# ESC.net
KiCad netlist of a schematic drawn in Altium Designer
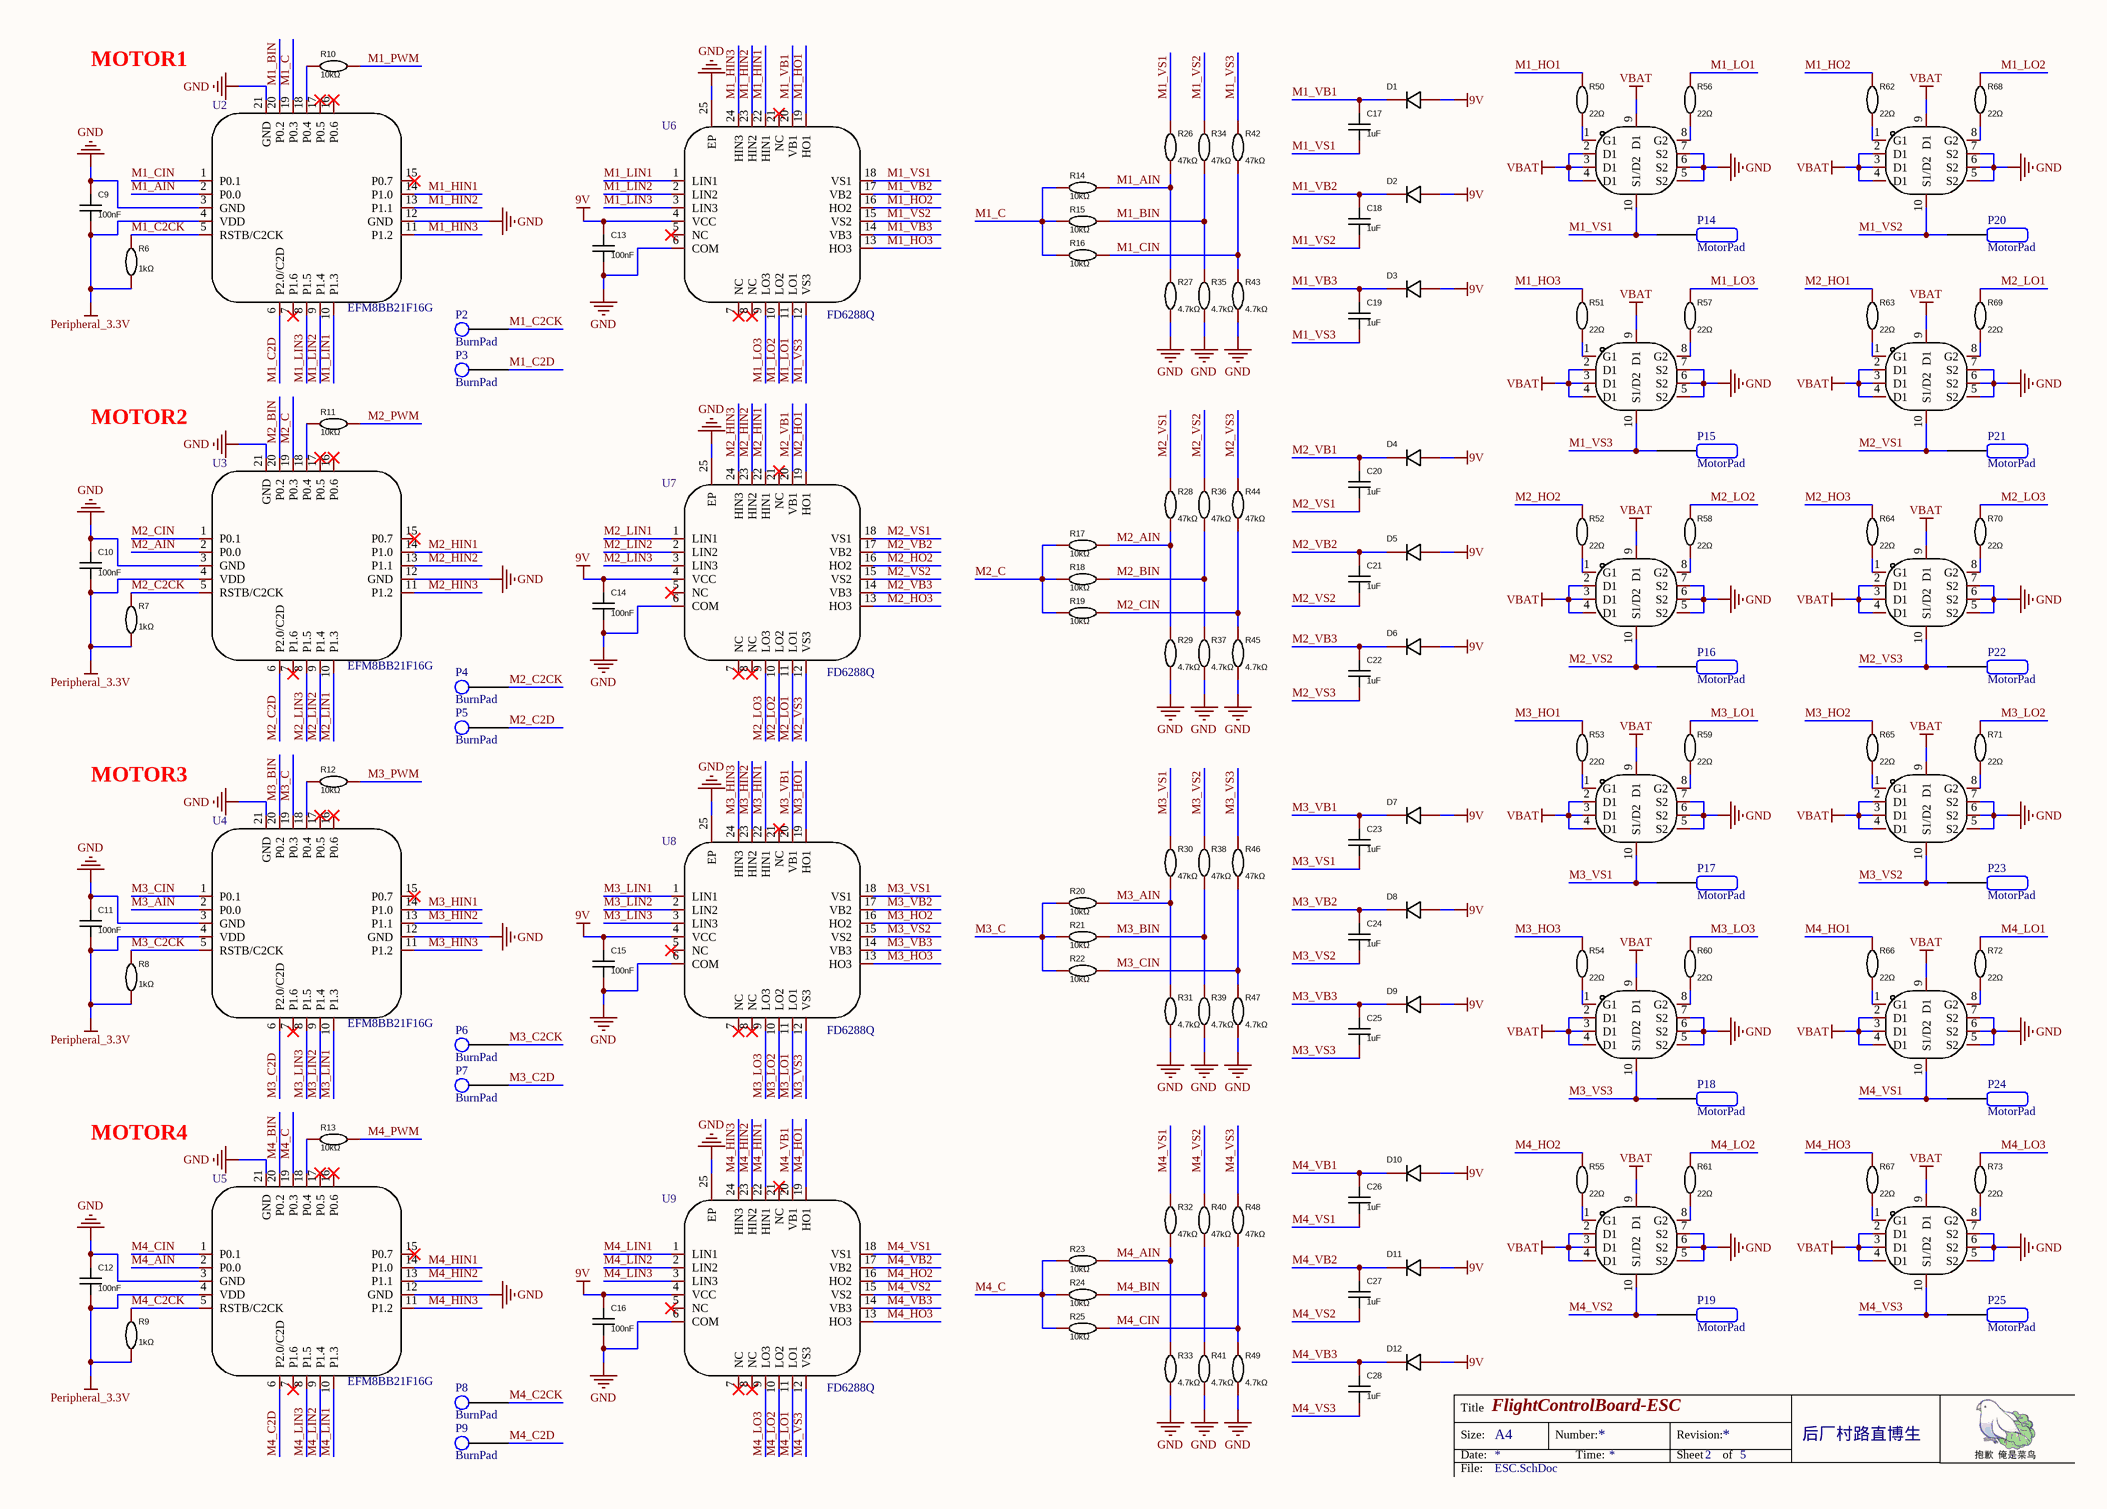
[diagram p0: ESC.SchDoc]

(export (version "E")
  (design (tool "Eeschema 10.0.6"))
  (components
    (comp (ref "C9")
      (value "100nF")
      (footprint "C0201")
      (libsource (lib "Capacitor") (part "CC0603KRX7R9BB104"))
    )
    (comp (ref "C10")
      (value "100nF")
      (footprint "C0201")
      (libsource (lib "Capacitor") (part "CC0603KRX7R9BB104"))
    )
    (comp (ref "C11")
      (value "100nF")
      (footprint "C0201")
      (libsource (lib "Capacitor") (part "CC0603KRX7R9BB104"))
    )
    (comp (ref "C12")
      (value "100nF")
      (footprint "C0201")
      (libsource (lib "Capacitor") (part "CC0603KRX7R9BB104"))
    )
    (comp (ref "C13")
      (value "100nF")
      (footprint "C0201")
      (libsource (lib "Capacitor") (part "CC0603KRX7R9BB104"))
    )
    (comp (ref "C14")
      (value "100nF")
      (footprint "C0201")
      (libsource (lib "Capacitor") (part "CC0603KRX7R9BB104"))
    )
    (comp (ref "C15")
      (value "100nF")
      (footprint "C0201")
      (libsource (lib "Capacitor") (part "CC0603KRX7R9BB104"))
    )
    (comp (ref "C16")
      (value "100nF")
      (footprint "C0201")
      (libsource (lib "Capacitor") (part "CC0603KRX7R9BB104"))
    )
    (comp (ref "C17")
      (value "1uF")
      (footprint "C0402")
      (libsource (lib "Capacitor") (part "CC0603KRX7R9BB104"))
    )
    (comp (ref "C18")
      (value "1uF")
      (footprint "C0402")
      (libsource (lib "Capacitor") (part "CC0603KRX7R9BB104"))
    )
    (comp (ref "C19")
      (value "1uF")
      (footprint "C0402")
      (libsource (lib "Capacitor") (part "CC0603KRX7R9BB104"))
    )
    (comp (ref "C20")
      (value "1uF")
      (footprint "C0402")
      (libsource (lib "Capacitor") (part "CC0603KRX7R9BB104"))
    )
    (comp (ref "C21")
      (value "1uF")
      (footprint "C0402")
      (libsource (lib "Capacitor") (part "CC0603KRX7R9BB104"))
    )
    (comp (ref "C22")
      (value "1uF")
      (footprint "C0402")
      (libsource (lib "Capacitor") (part "CC0603KRX7R9BB104"))
    )
    (comp (ref "C23")
      (value "1uF")
      (footprint "C0402")
      (libsource (lib "Capacitor") (part "CC0603KRX7R9BB104"))
    )
    (comp (ref "C24")
      (value "1uF")
      (footprint "C0402")
      (libsource (lib "Capacitor") (part "CC0603KRX7R9BB104"))
    )
    (comp (ref "C25")
      (value "1uF")
      (footprint "C0402")
      (libsource (lib "Capacitor") (part "CC0603KRX7R9BB104"))
    )
    (comp (ref "C26")
      (value "1uF")
      (footprint "C0402")
      (libsource (lib "Capacitor") (part "CC0603KRX7R9BB104"))
    )
    (comp (ref "C27")
      (value "1uF")
      (footprint "C0402")
      (libsource (lib "Capacitor") (part "CC0603KRX7R9BB104"))
    )
    (comp (ref "C28")
      (value "1uF")
      (footprint "C0402")
      (libsource (lib "Capacitor") (part "CC0603KRX7R9BB104"))
    )
    (comp (ref "D1")
      (value "1N4148WT T4")
      (footprint "SOD-523")
      (fields (field (name "MANUFACTURER") "CJ(江苏长电/长晶)"))
      (libsource (lib "Diode") (part "1N4148WT T4"))
    )
    (comp (ref "D2")
      (value "1N4148WT T4")
      (footprint "SOD-523")
      (fields (field (name "MANUFACTURER") "CJ(江苏长电/长晶)"))
      (libsource (lib "Diode") (part "1N4148WT T4"))
    )
    (comp (ref "D3")
      (value "1N4148WT T4")
      (footprint "SOD-523")
      (fields (field (name "MANUFACTURER") "CJ(江苏长电/长晶)"))
      (libsource (lib "Diode") (part "1N4148WT T4"))
    )
    (comp (ref "D4")
      (value "1N4148WT T4")
      (footprint "SOD-523")
      (fields (field (name "MANUFACTURER") "CJ(江苏长电/长晶)"))
      (libsource (lib "Diode") (part "1N4148WT T4"))
    )
    (comp (ref "D5")
      (value "1N4148WT T4")
      (footprint "SOD-523")
      (fields (field (name "MANUFACTURER") "CJ(江苏长电/长晶)"))
      (libsource (lib "Diode") (part "1N4148WT T4"))
    )
    (comp (ref "D6")
      (value "1N4148WT T4")
      (footprint "SOD-523")
      (fields (field (name "MANUFACTURER") "CJ(江苏长电/长晶)"))
      (libsource (lib "Diode") (part "1N4148WT T4"))
    )
    (comp (ref "D7")
      (value "1N4148WT T4")
      (footprint "SOD-523")
      (fields (field (name "MANUFACTURER") "CJ(江苏长电/长晶)"))
      (libsource (lib "Diode") (part "1N4148WT T4"))
    )
    (comp (ref "D8")
      (value "1N4148WT T4")
      (footprint "SOD-523")
      (fields (field (name "MANUFACTURER") "CJ(江苏长电/长晶)"))
      (libsource (lib "Diode") (part "1N4148WT T4"))
    )
    (comp (ref "D9")
      (value "1N4148WT T4")
      (footprint "SOD-523")
      (fields (field (name "MANUFACTURER") "CJ(江苏长电/长晶)"))
      (libsource (lib "Diode") (part "1N4148WT T4"))
    )
    (comp (ref "D10")
      (value "1N4148WT T4")
      (footprint "SOD-523")
      (fields (field (name "MANUFACTURER") "CJ(江苏长电/长晶)"))
      (libsource (lib "Diode") (part "1N4148WT T4"))
    )
    (comp (ref "D11")
      (value "1N4148WT T4")
      (footprint "SOD-523")
      (fields (field (name "MANUFACTURER") "CJ(江苏长电/长晶)"))
      (libsource (lib "Diode") (part "1N4148WT T4"))
    )
    (comp (ref "D12")
      (value "1N4148WT T4")
      (footprint "SOD-523")
      (fields (field (name "MANUFACTURER") "CJ(江苏长电/长晶)"))
      (libsource (lib "Diode") (part "1N4148WT T4"))
    )
    (comp (ref "P2") (value "BurnPad") (footprint "BurnPad_0.5mm") (libsource (lib "Pad") (part "BurnPad")))
    (comp (ref "P3") (value "BurnPad") (footprint "BurnPad_0.5mm") (libsource (lib "Pad") (part "BurnPad")))
    (comp (ref "P4") (value "BurnPad") (footprint "BurnPad_0.5mm") (libsource (lib "Pad") (part "BurnPad")))
    (comp (ref "P5") (value "BurnPad") (footprint "BurnPad_0.5mm") (libsource (lib "Pad") (part "BurnPad")))
    (comp (ref "P6") (value "BurnPad") (footprint "BurnPad_0.5mm") (libsource (lib "Pad") (part "BurnPad")))
    (comp (ref "P7") (value "BurnPad") (footprint "BurnPad_0.5mm") (libsource (lib "Pad") (part "BurnPad")))
    (comp (ref "P8") (value "BurnPad") (footprint "BurnPad_0.5mm") (libsource (lib "Pad") (part "BurnPad")))
    (comp (ref "P9") (value "BurnPad") (footprint "BurnPad_0.5mm") (libsource (lib "Pad") (part "BurnPad")))
    (comp (ref "P14")
      (value "MotorPad")
      (footprint "MOTOR HALF HOLE")
      (libsource (lib "Pad") (part "MotorPad"))
    )
    (comp (ref "P15")
      (value "MotorPad")
      (footprint "MOTOR HALF HOLE")
      (libsource (lib "Pad") (part "MotorPad"))
    )
    (comp (ref "P16")
      (value "MotorPad")
      (footprint "MOTOR HALF HOLE")
      (libsource (lib "Pad") (part "MotorPad"))
    )
    (comp (ref "P17")
      (value "MotorPad")
      (footprint "MOTOR HALF HOLE")
      (libsource (lib "Pad") (part "MotorPad"))
    )
    (comp (ref "P18")
      (value "MotorPad")
      (footprint "MOTOR HALF HOLE")
      (libsource (lib "Pad") (part "MotorPad"))
    )
    (comp (ref "P19")
      (value "MotorPad")
      (footprint "MOTOR HALF HOLE")
      (libsource (lib "Pad") (part "MotorPad"))
    )
    (comp (ref "P20")
      (value "MotorPad")
      (footprint "MOTOR HALF HOLE")
      (libsource (lib "Pad") (part "MotorPad"))
    )
    (comp (ref "P21")
      (value "MotorPad")
      (footprint "MOTOR HALF HOLE")
      (libsource (lib "Pad") (part "MotorPad"))
    )
    (comp (ref "P22")
      (value "MotorPad")
      (footprint "MOTOR HALF HOLE")
      (libsource (lib "Pad") (part "MotorPad"))
    )
    (comp (ref "P23")
      (value "MotorPad")
      (footprint "MOTOR HALF HOLE")
      (libsource (lib "Pad") (part "MotorPad"))
    )
    (comp (ref "P24")
      (value "MotorPad")
      (footprint "MOTOR HALF HOLE")
      (libsource (lib "Pad") (part "MotorPad"))
    )
    (comp (ref "P25")
      (value "MotorPad")
      (footprint "MOTOR HALF HOLE")
      (libsource (lib "Pad") (part "MotorPad"))
    )
    (comp (ref "Q1")
      (value "AON7934")
      (footprint "DFN-8")
      (fields (field (name "MANUFACTURER") "AOS"))
      (libsource (lib "MOS") (part "AON7934"))
    )
    (comp (ref "Q2")
      (value "AON7934")
      (footprint "DFN-8")
      (fields (field (name "MANUFACTURER") "AOS"))
      (libsource (lib "MOS") (part "AON7934"))
    )
    (comp (ref "Q3")
      (value "AON7934")
      (footprint "DFN-8")
      (fields (field (name "MANUFACTURER") "AOS"))
      (libsource (lib "MOS") (part "AON7934"))
    )
    (comp (ref "Q4")
      (value "AON7934")
      (footprint "DFN-8")
      (fields (field (name "MANUFACTURER") "AOS"))
      (libsource (lib "MOS") (part "AON7934"))
    )
    (comp (ref "Q5")
      (value "AON7934")
      (footprint "DFN-8")
      (fields (field (name "MANUFACTURER") "AOS"))
      (libsource (lib "MOS") (part "AON7934"))
    )
    (comp (ref "Q6")
      (value "AON7934")
      (footprint "DFN-8")
      (fields (field (name "MANUFACTURER") "AOS"))
      (libsource (lib "MOS") (part "AON7934"))
    )
    (comp (ref "Q7")
      (value "AON7934")
      (footprint "DFN-8")
      (fields (field (name "MANUFACTURER") "AOS"))
      (libsource (lib "MOS") (part "AON7934"))
    )
    (comp (ref "Q8")
      (value "AON7934")
      (footprint "DFN-8")
      (fields (field (name "MANUFACTURER") "AOS"))
      (libsource (lib "MOS") (part "AON7934"))
    )
    (comp (ref "Q9")
      (value "AON7934")
      (footprint "DFN-8")
      (fields (field (name "MANUFACTURER") "AOS"))
      (libsource (lib "MOS") (part "AON7934"))
    )
    (comp (ref "Q10")
      (value "AON7934")
      (footprint "DFN-8")
      (fields (field (name "MANUFACTURER") "AOS"))
      (libsource (lib "MOS") (part "AON7934"))
    )
    (comp (ref "Q11")
      (value "AON7934")
      (footprint "DFN-8")
      (fields (field (name "MANUFACTURER") "AOS"))
      (libsource (lib "MOS") (part "AON7934"))
    )
    (comp (ref "Q12")
      (value "AON7934")
      (footprint "DFN-8")
      (fields (field (name "MANUFACTURER") "AOS"))
      (libsource (lib "MOS") (part "AON7934"))
    )
    (comp (ref "R6") (value "1kΩ") (footprint "R0201") (libsource (lib "Resistor") (part "0603WAF1002T5E")))
    (comp (ref "R7") (value "1kΩ") (footprint "R0201") (libsource (lib "Resistor") (part "0603WAF1002T5E")))
    (comp (ref "R8") (value "1kΩ") (footprint "R0201") (libsource (lib "Resistor") (part "0603WAF1002T5E")))
    (comp (ref "R9") (value "1kΩ") (footprint "R0201") (libsource (lib "Resistor") (part "0603WAF1002T5E")))
    (comp (ref "R10") (value "10kΩ") (footprint "R0201") (libsource (lib "Resistor") (part "0603WAF1002T5E")))
    (comp (ref "R11") (value "10kΩ") (footprint "R0201") (libsource (lib "Resistor") (part "0603WAF1002T5E")))
    (comp (ref "R12") (value "10kΩ") (footprint "R0201") (libsource (lib "Resistor") (part "0603WAF1002T5E")))
    (comp (ref "R13") (value "10kΩ") (footprint "R0201") (libsource (lib "Resistor") (part "0603WAF1002T5E")))
    (comp (ref "R14") (value "10kΩ") (footprint "R0201") (libsource (lib "Resistor") (part "0603WAF1002T5E")))
    (comp (ref "R15") (value "10kΩ") (footprint "R0201") (libsource (lib "Resistor") (part "0603WAF1002T5E")))
    (comp (ref "R16") (value "10kΩ") (footprint "R0201") (libsource (lib "Resistor") (part "0603WAF1002T5E")))
    (comp (ref "R17") (value "10kΩ") (footprint "R0201") (libsource (lib "Resistor") (part "0603WAF1002T5E")))
    (comp (ref "R18") (value "10kΩ") (footprint "R0201") (libsource (lib "Resistor") (part "0603WAF1002T5E")))
    (comp (ref "R19") (value "10kΩ") (footprint "R0201") (libsource (lib "Resistor") (part "0603WAF1002T5E")))
    (comp (ref "R20") (value "10kΩ") (footprint "R0201") (libsource (lib "Resistor") (part "0603WAF1002T5E")))
    (comp (ref "R21") (value "10kΩ") (footprint "R0201") (libsource (lib "Resistor") (part "0603WAF1002T5E")))
    (comp (ref "R22") (value "10kΩ") (footprint "R0201") (libsource (lib "Resistor") (part "0603WAF1002T5E")))
    (comp (ref "R23") (value "10kΩ") (footprint "R0201") (libsource (lib "Resistor") (part "0603WAF1002T5E")))
    (comp (ref "R24") (value "10kΩ") (footprint "R0201") (libsource (lib "Resistor") (part "0603WAF1002T5E")))
    (comp (ref "R25") (value "10kΩ") (footprint "R0201") (libsource (lib "Resistor") (part "0603WAF1002T5E")))
    (comp (ref "R26") (value "47kΩ") (footprint "R0201") (libsource (lib "Resistor") (part "0603WAF1002T5E")))
    (comp (ref "R27")
      (value "4.7kΩ")
      (footprint "R0201")
      (libsource (lib "Resistor") (part "0603WAF1002T5E"))
    )
    (comp (ref "R28") (value "47kΩ") (footprint "R0201") (libsource (lib "Resistor") (part "0603WAF1002T5E")))
    (comp (ref "R29")
      (value "4.7kΩ")
      (footprint "R0201")
      (libsource (lib "Resistor") (part "0603WAF1002T5E"))
    )
    (comp (ref "R30") (value "47kΩ") (footprint "R0201") (libsource (lib "Resistor") (part "0603WAF1002T5E")))
    (comp (ref "R31")
      (value "4.7kΩ")
      (footprint "R0201")
      (libsource (lib "Resistor") (part "0603WAF1002T5E"))
    )
    (comp (ref "R32") (value "47kΩ") (footprint "R0201") (libsource (lib "Resistor") (part "0603WAF1002T5E")))
    (comp (ref "R33")
      (value "4.7kΩ")
      (footprint "R0201")
      (libsource (lib "Resistor") (part "0603WAF1002T5E"))
    )
    (comp (ref "R34") (value "47kΩ") (footprint "R0201") (libsource (lib "Resistor") (part "0603WAF1002T5E")))
    (comp (ref "R35")
      (value "4.7kΩ")
      (footprint "R0201")
      (libsource (lib "Resistor") (part "0603WAF1002T5E"))
    )
    (comp (ref "R36") (value "47kΩ") (footprint "R0201") (libsource (lib "Resistor") (part "0603WAF1002T5E")))
    (comp (ref "R37")
      (value "4.7kΩ")
      (footprint "R0201")
      (libsource (lib "Resistor") (part "0603WAF1002T5E"))
    )
    (comp (ref "R38") (value "47kΩ") (footprint "R0201") (libsource (lib "Resistor") (part "0603WAF1002T5E")))
    (comp (ref "R39")
      (value "4.7kΩ")
      (footprint "R0201")
      (libsource (lib "Resistor") (part "0603WAF1002T5E"))
    )
    (comp (ref "R40") (value "47kΩ") (footprint "R0201") (libsource (lib "Resistor") (part "0603WAF1002T5E")))
    (comp (ref "R41")
      (value "4.7kΩ")
      (footprint "R0201")
      (libsource (lib "Resistor") (part "0603WAF1002T5E"))
    )
    (comp (ref "R42") (value "47kΩ") (footprint "R0201") (libsource (lib "Resistor") (part "0603WAF1002T5E")))
    (comp (ref "R43")
      (value "4.7kΩ")
      (footprint "R0201")
      (libsource (lib "Resistor") (part "0603WAF1002T5E"))
    )
    (comp (ref "R44") (value "47kΩ") (footprint "R0201") (libsource (lib "Resistor") (part "0603WAF1002T5E")))
    (comp (ref "R45")
      (value "4.7kΩ")
      (footprint "R0201")
      (libsource (lib "Resistor") (part "0603WAF1002T5E"))
    )
    (comp (ref "R46") (value "47kΩ") (footprint "R0201") (libsource (lib "Resistor") (part "0603WAF1002T5E")))
    (comp (ref "R47")
      (value "4.7kΩ")
      (footprint "R0201")
      (libsource (lib "Resistor") (part "0603WAF1002T5E"))
    )
    (comp (ref "R48") (value "47kΩ") (footprint "R0201") (libsource (lib "Resistor") (part "0603WAF1002T5E")))
    (comp (ref "R49")
      (value "4.7kΩ")
      (footprint "R0201")
      (libsource (lib "Resistor") (part "0603WAF1002T5E"))
    )
    (comp (ref "R50") (value "22Ω") (footprint "R0201") (libsource (lib "Resistor") (part "0603WAF1002T5E")))
    (comp (ref "R51") (value "22Ω") (footprint "R0201") (libsource (lib "Resistor") (part "0603WAF1002T5E")))
    (comp (ref "R52") (value "22Ω") (footprint "R0201") (libsource (lib "Resistor") (part "0603WAF1002T5E")))
    (comp (ref "R53") (value "22Ω") (footprint "R0201") (libsource (lib "Resistor") (part "0603WAF1002T5E")))
    (comp (ref "R54") (value "22Ω") (footprint "R0201") (libsource (lib "Resistor") (part "0603WAF1002T5E")))
    (comp (ref "R55") (value "22Ω") (footprint "R0201") (libsource (lib "Resistor") (part "0603WAF1002T5E")))
    (comp (ref "R56") (value "22Ω") (footprint "R0201") (libsource (lib "Resistor") (part "0603WAF1002T5E")))
    (comp (ref "R57") (value "22Ω") (footprint "R0201") (libsource (lib "Resistor") (part "0603WAF1002T5E")))
    (comp (ref "R58") (value "22Ω") (footprint "R0201") (libsource (lib "Resistor") (part "0603WAF1002T5E")))
    (comp (ref "R59") (value "22Ω") (footprint "R0201") (libsource (lib "Resistor") (part "0603WAF1002T5E")))
    (comp (ref "R60") (value "22Ω") (footprint "R0201") (libsource (lib "Resistor") (part "0603WAF1002T5E")))
    (comp (ref "R61") (value "22Ω") (footprint "R0201") (libsource (lib "Resistor") (part "0603WAF1002T5E")))
    (comp (ref "R62") (value "22Ω") (footprint "R0201") (libsource (lib "Resistor") (part "0603WAF1002T5E")))
    (comp (ref "R63") (value "22Ω") (footprint "R0201") (libsource (lib "Resistor") (part "0603WAF1002T5E")))
    (comp (ref "R64") (value "22Ω") (footprint "R0201") (libsource (lib "Resistor") (part "0603WAF1002T5E")))
    (comp (ref "R65") (value "22Ω") (footprint "R0201") (libsource (lib "Resistor") (part "0603WAF1002T5E")))
    (comp (ref "R66") (value "22Ω") (footprint "R0201") (libsource (lib "Resistor") (part "0603WAF1002T5E")))
    (comp (ref "R67") (value "22Ω") (footprint "R0201") (libsource (lib "Resistor") (part "0603WAF1002T5E")))
    (comp (ref "R68") (value "22Ω") (footprint "R0201") (libsource (lib "Resistor") (part "0603WAF1002T5E")))
    (comp (ref "R69") (value "22Ω") (footprint "R0201") (libsource (lib "Resistor") (part "0603WAF1002T5E")))
    (comp (ref "R70") (value "22Ω") (footprint "R0201") (libsource (lib "Resistor") (part "0603WAF1002T5E")))
    (comp (ref "R71") (value "22Ω") (footprint "R0201") (libsource (lib "Resistor") (part "0603WAF1002T5E")))
    (comp (ref "R72") (value "22Ω") (footprint "R0201") (libsource (lib "Resistor") (part "0603WAF1002T5E")))
    (comp (ref "R73") (value "22Ω") (footprint "R0201") (libsource (lib "Resistor") (part "0603WAF1002T5E")))
    (comp (ref "U2")
      (value "EFM8BB21F16G")
      (footprint "QFN-20_L3.0-W3.0-P0.50-BL-EP1.7_EFM8BB21F16G")
      (fields
        (field (name "MANUFACTURER") "SILICON LABS(芯科)")
        (field (name "MANUFACTURER PART") "EFM8BB21F16G-C-QFN20R")
      )
      (libsource (lib "ESC_Drive") (part "EFM8BB21F16G"))
    )
    (comp (ref "U3")
      (value "EFM8BB21F16G")
      (footprint "QFN-20_L3.0-W3.0-P0.50-BL-EP1.7_EFM8BB21F16G")
      (fields
        (field (name "MANUFACTURER") "SILICON LABS(芯科)")
        (field (name "MANUFACTURER PART") "EFM8BB21F16G-C-QFN20R")
      )
      (libsource (lib "ESC_Drive") (part "EFM8BB21F16G"))
    )
    (comp (ref "U4")
      (value "EFM8BB21F16G")
      (footprint "QFN-20_L3.0-W3.0-P0.50-BL-EP1.7_EFM8BB21F16G")
      (fields
        (field (name "MANUFACTURER") "SILICON LABS(芯科)")
        (field (name "MANUFACTURER PART") "EFM8BB21F16G-C-QFN20R")
      )
      (libsource (lib "ESC_Drive") (part "EFM8BB21F16G"))
    )
    (comp (ref "U5")
      (value "EFM8BB21F16G")
      (footprint "QFN-20_L3.0-W3.0-P0.50-BL-EP1.7_EFM8BB21F16G")
      (fields
        (field (name "MANUFACTURER") "SILICON LABS(芯科)")
        (field (name "MANUFACTURER PART") "EFM8BB21F16G-C-QFN20R")
      )
      (libsource (lib "ESC_Drive") (part "EFM8BB21F16G"))
    )
    (comp (ref "U6")
      (value "FD6288Q")
      (footprint "QFN-24_L4.0-W4.0-P0.50-BL-EP2.6")
      (fields (field (name "MANUFACTURER") "Fortior Tech(峰岹)"))
      (libsource (lib "ESC_Drive") (part "FD6288Q"))
    )
    (comp (ref "U7")
      (value "FD6288Q")
      (footprint "QFN-24_L4.0-W4.0-P0.50-BL-EP2.6")
      (fields (field (name "MANUFACTURER") "Fortior Tech(峰岹)"))
      (libsource (lib "ESC_Drive") (part "FD6288Q"))
    )
    (comp (ref "U8")
      (value "FD6288Q")
      (footprint "QFN-24_L4.0-W4.0-P0.50-BL-EP2.6")
      (fields (field (name "MANUFACTURER") "Fortior Tech(峰岹)"))
      (libsource (lib "ESC_Drive") (part "FD6288Q"))
    )
    (comp (ref "U9")
      (value "FD6288Q")
      (footprint "QFN-24_L4.0-W4.0-P0.50-BL-EP2.6")
      (fields (field (name "MANUFACTURER") "Fortior Tech(峰岹)"))
      (libsource (lib "ESC_Drive") (part "FD6288Q"))
    )
  )
  (nets
    (net (code "1") (name "/M1_AIN") (class "Default")
      (node (ref "R14") (pin "2") (pinfunction "2_2") (pintype "passive"))
      (node (ref "R26") (pin "1") (pinfunction "1_1") (pintype "passive"))
      (node (ref "R27") (pin "2") (pinfunction "2_2") (pintype "passive"))
      (node (ref "U2") (pin "2") (pinfunction "P0.0_2") (pintype "passive"))
    )
    (net (code "2") (name "/M1_BIN") (class "Default")
      (node (ref "R15") (pin "2") (pinfunction "2_2") (pintype "passive"))
      (node (ref "R34") (pin "1") (pinfunction "1_1") (pintype "passive"))
      (node (ref "R35") (pin "2") (pinfunction "2_2") (pintype "passive"))
      (node (ref "U2") (pin "20") (pinfunction "P0.2_20") (pintype "passive"))
    )
    (net (code "3") (name "/M1_C") (class "Default")
      (node (ref "R14") (pin "1") (pinfunction "1_1") (pintype "passive"))
      (node (ref "R15") (pin "1") (pinfunction "1_1") (pintype "passive"))
      (node (ref "R16") (pin "1") (pinfunction "1_1") (pintype "passive"))
      (node (ref "U2") (pin "19") (pinfunction "P0.3_19") (pintype "passive"))
    )
    (net (code "4") (name "/M1_C2CK") (class "Default")
      (node (ref "P2") (pin "1") (pinfunction "1_1") (pintype "passive"))
      (node (ref "R6") (pin "2") (pinfunction "2_2") (pintype "passive"))
      (node (ref "U2") (pin "5") (pinfunction "RSTB/C2CK_5") (pintype "passive"))
    )
    (net (code "5") (name "/M1_C2D") (class "Default")
      (node (ref "P3") (pin "1") (pinfunction "1_1") (pintype "passive"))
      (node (ref "U2") (pin "6") (pinfunction "P2.0/C2D_6") (pintype "passive"))
    )
    (net (code "6") (name "/M1_CIN") (class "Default")
      (node (ref "R16") (pin "2") (pinfunction "2_2") (pintype "passive"))
      (node (ref "R42") (pin "1") (pinfunction "1_1") (pintype "passive"))
      (node (ref "R43") (pin "2") (pinfunction "2_2") (pintype "passive"))
      (node (ref "U2") (pin "1") (pinfunction "P0.1_1") (pintype "passive"))
    )
    (net (code "7") (name "/M1_HIN1") (class "Default")
      (node (ref "U2") (pin "14") (pinfunction "P1.0_14") (pintype "passive"))
      (node (ref "U6") (pin "22") (pinfunction "HIN1_22") (pintype "passive"))
    )
    (net (code "8") (name "/M1_HIN2") (class "Default")
      (node (ref "U2") (pin "13") (pinfunction "P1.1_13") (pintype "passive"))
      (node (ref "U6") (pin "23") (pinfunction "HIN2_23") (pintype "passive"))
    )
    (net (code "9") (name "/M1_HIN3") (class "Default")
      (node (ref "U2") (pin "11") (pinfunction "P1.2_11") (pintype "passive"))
      (node (ref "U6") (pin "24") (pinfunction "HIN3_24") (pintype "passive"))
    )
    (net (code "10") (name "/M1_HO1") (class "Default")
      (node (ref "R50") (pin "2") (pinfunction "2_2") (pintype "passive"))
      (node (ref "U6") (pin "19") (pinfunction "HO1_19") (pintype "passive"))
    )
    (net (code "11") (name "/M1_HO2") (class "Default")
      (node (ref "R62") (pin "2") (pinfunction "2_2") (pintype "passive"))
      (node (ref "U6") (pin "16") (pinfunction "HO2_16") (pintype "passive"))
    )
    (net (code "12") (name "/M1_HO3") (class "Default")
      (node (ref "R51") (pin "2") (pinfunction "2_2") (pintype "passive"))
      (node (ref "U6") (pin "13") (pinfunction "HO3_13") (pintype "passive"))
    )
    (net (code "13") (name "/M1_LIN1") (class "Default")
      (node (ref "U2") (pin "10") (pinfunction "P1.3_10") (pintype "passive"))
      (node (ref "U6") (pin "1") (pinfunction "LIN1_1") (pintype "passive"))
    )
    (net (code "14") (name "/M1_LIN2") (class "Default")
      (node (ref "U2") (pin "9") (pinfunction "P1.4_9") (pintype "passive"))
      (node (ref "U6") (pin "2") (pinfunction "LIN2_2") (pintype "passive"))
    )
    (net (code "15") (name "/M1_LIN3") (class "Default")
      (node (ref "U2") (pin "8") (pinfunction "P1.5_8") (pintype "passive"))
      (node (ref "U6") (pin "3") (pinfunction "LIN3_3") (pintype "passive"))
    )
    (net (code "16") (name "/M1_LO1") (class "Default")
      (node (ref "R56") (pin "2") (pinfunction "2_2") (pintype "passive"))
      (node (ref "U6") (pin "11") (pinfunction "LO1_11") (pintype "passive"))
    )
    (net (code "17") (name "/M1_LO2") (class "Default")
      (node (ref "R68") (pin "2") (pinfunction "2_2") (pintype "passive"))
      (node (ref "U6") (pin "10") (pinfunction "LO2_10") (pintype "passive"))
    )
    (net (code "18") (name "/M1_LO3") (class "Default")
      (node (ref "R57") (pin "2") (pinfunction "2_2") (pintype "passive"))
      (node (ref "U6") (pin "9") (pinfunction "LO3_9") (pintype "passive"))
    )
    (net (code "19") (name "/M1_PWM") (class "Default")
      (node (ref "R10") (pin "2") (pinfunction "2_2") (pintype "passive"))
    )
    (net (code "20") (name "/M1_VB1") (class "Default")
      (node (ref "C17") (pin "2") (pinfunction "2_2") (pintype "passive"))
      (node (ref "D1") (pin "1") (pinfunction "K_1") (pintype "passive"))
      (node (ref "U6") (pin "20") (pinfunction "VB1_20") (pintype "passive"))
    )
    (net (code "21") (name "/M1_VB2") (class "Default")
      (node (ref "C18") (pin "2") (pinfunction "2_2") (pintype "passive"))
      (node (ref "D2") (pin "1") (pinfunction "K_1") (pintype "passive"))
      (node (ref "U6") (pin "17") (pinfunction "VB2_17") (pintype "passive"))
    )
    (net (code "22") (name "/M1_VB3") (class "Default")
      (node (ref "C19") (pin "2") (pinfunction "2_2") (pintype "passive"))
      (node (ref "D3") (pin "1") (pinfunction "K_1") (pintype "passive"))
      (node (ref "U6") (pin "14") (pinfunction "VB3_14") (pintype "passive"))
    )
    (net (code "23") (name "/M1_VS1") (class "Default")
      (node (ref "C17") (pin "1") (pinfunction "1_1") (pintype "passive"))
      (node (ref "P14") (pin "1") (pinfunction "1_1") (pintype "passive"))
      (node (ref "Q1") (pin "10") (pinfunction "S1/D2_10") (pintype "passive"))
      (node (ref "R26") (pin "2") (pinfunction "2_2") (pintype "passive"))
      (node (ref "U6") (pin "18") (pinfunction "VS1_18") (pintype "passive"))
    )
    (net (code "24") (name "/M1_VS2") (class "Default")
      (node (ref "C18") (pin "1") (pinfunction "1_1") (pintype "passive"))
      (node (ref "P20") (pin "1") (pinfunction "1_1") (pintype "passive"))
      (node (ref "Q7") (pin "10") (pinfunction "S1/D2_10") (pintype "passive"))
      (node (ref "R34") (pin "2") (pinfunction "2_2") (pintype "passive"))
      (node (ref "U6") (pin "15") (pinfunction "VS2_15") (pintype "passive"))
    )
    (net (code "25") (name "/M1_VS3") (class "Default")
      (node (ref "C19") (pin "1") (pinfunction "1_1") (pintype "passive"))
      (node (ref "P15") (pin "1") (pinfunction "1_1") (pintype "passive"))
      (node (ref "Q2") (pin "10") (pinfunction "S1/D2_10") (pintype "passive"))
      (node (ref "R42") (pin "2") (pinfunction "2_2") (pintype "passive"))
      (node (ref "U6") (pin "12") (pinfunction "VS3_12") (pintype "passive"))
    )
    (net (code "26") (name "/M2_AIN") (class "Default")
      (node (ref "R17") (pin "2") (pinfunction "2_2") (pintype "passive"))
      (node (ref "R28") (pin "1") (pinfunction "1_1") (pintype "passive"))
      (node (ref "R29") (pin "2") (pinfunction "2_2") (pintype "passive"))
      (node (ref "U3") (pin "2") (pinfunction "P0.0_2") (pintype "passive"))
    )
    (net (code "27") (name "/M2_BIN") (class "Default")
      (node (ref "R18") (pin "2") (pinfunction "2_2") (pintype "passive"))
      (node (ref "R36") (pin "1") (pinfunction "1_1") (pintype "passive"))
      (node (ref "R37") (pin "2") (pinfunction "2_2") (pintype "passive"))
      (node (ref "U3") (pin "20") (pinfunction "P0.2_20") (pintype "passive"))
    )
    (net (code "28") (name "/M2_C") (class "Default")
      (node (ref "R17") (pin "1") (pinfunction "1_1") (pintype "passive"))
      (node (ref "R18") (pin "1") (pinfunction "1_1") (pintype "passive"))
      (node (ref "R19") (pin "1") (pinfunction "1_1") (pintype "passive"))
      (node (ref "U3") (pin "19") (pinfunction "P0.3_19") (pintype "passive"))
    )
    (net (code "29") (name "/M2_C2CK") (class "Default")
      (node (ref "P4") (pin "1") (pinfunction "1_1") (pintype "passive"))
      (node (ref "R7") (pin "2") (pinfunction "2_2") (pintype "passive"))
      (node (ref "U3") (pin "5") (pinfunction "RSTB/C2CK_5") (pintype "passive"))
    )
    (net (code "30") (name "/M2_C2D") (class "Default")
      (node (ref "P5") (pin "1") (pinfunction "1_1") (pintype "passive"))
      (node (ref "U3") (pin "6") (pinfunction "P2.0/C2D_6") (pintype "passive"))
    )
    (net (code "31") (name "/M2_CIN") (class "Default")
      (node (ref "R19") (pin "2") (pinfunction "2_2") (pintype "passive"))
      (node (ref "R44") (pin "1") (pinfunction "1_1") (pintype "passive"))
      (node (ref "R45") (pin "2") (pinfunction "2_2") (pintype "passive"))
      (node (ref "U3") (pin "1") (pinfunction "P0.1_1") (pintype "passive"))
    )
    (net (code "32") (name "/M2_HIN1") (class "Default")
      (node (ref "U3") (pin "14") (pinfunction "P1.0_14") (pintype "passive"))
      (node (ref "U7") (pin "22") (pinfunction "HIN1_22") (pintype "passive"))
    )
    (net (code "33") (name "/M2_HIN2") (class "Default")
      (node (ref "U3") (pin "13") (pinfunction "P1.1_13") (pintype "passive"))
      (node (ref "U7") (pin "23") (pinfunction "HIN2_23") (pintype "passive"))
    )
    (net (code "34") (name "/M2_HIN3") (class "Default")
      (node (ref "U3") (pin "11") (pinfunction "P1.2_11") (pintype "passive"))
      (node (ref "U7") (pin "24") (pinfunction "HIN3_24") (pintype "passive"))
    )
    (net (code "35") (name "/M2_HO1") (class "Default")
      (node (ref "R63") (pin "2") (pinfunction "2_2") (pintype "passive"))
      (node (ref "U7") (pin "19") (pinfunction "HO1_19") (pintype "passive"))
    )
    (net (code "36") (name "/M2_HO2") (class "Default")
      (node (ref "R52") (pin "2") (pinfunction "2_2") (pintype "passive"))
      (node (ref "U7") (pin "16") (pinfunction "HO2_16") (pintype "passive"))
    )
    (net (code "37") (name "/M2_HO3") (class "Default")
      (node (ref "R64") (pin "2") (pinfunction "2_2") (pintype "passive"))
      (node (ref "U7") (pin "13") (pinfunction "HO3_13") (pintype "passive"))
    )
    (net (code "38") (name "/M2_LIN1") (class "Default")
      (node (ref "U3") (pin "10") (pinfunction "P1.3_10") (pintype "passive"))
      (node (ref "U7") (pin "1") (pinfunction "LIN1_1") (pintype "passive"))
    )
    (net (code "39") (name "/M2_LIN2") (class "Default")
      (node (ref "U3") (pin "9") (pinfunction "P1.4_9") (pintype "passive"))
      (node (ref "U7") (pin "2") (pinfunction "LIN2_2") (pintype "passive"))
    )
    (net (code "40") (name "/M2_LIN3") (class "Default")
      (node (ref "U3") (pin "8") (pinfunction "P1.5_8") (pintype "passive"))
      (node (ref "U7") (pin "3") (pinfunction "LIN3_3") (pintype "passive"))
    )
    (net (code "41") (name "/M2_LO1") (class "Default")
      (node (ref "R69") (pin "2") (pinfunction "2_2") (pintype "passive"))
      (node (ref "U7") (pin "11") (pinfunction "LO1_11") (pintype "passive"))
    )
    (net (code "42") (name "/M2_LO2") (class "Default")
      (node (ref "R58") (pin "2") (pinfunction "2_2") (pintype "passive"))
      (node (ref "U7") (pin "10") (pinfunction "LO2_10") (pintype "passive"))
    )
    (net (code "43") (name "/M2_LO3") (class "Default")
      (node (ref "R70") (pin "2") (pinfunction "2_2") (pintype "passive"))
      (node (ref "U7") (pin "9") (pinfunction "LO3_9") (pintype "passive"))
    )
    (net (code "44") (name "/M2_PWM") (class "Default")
      (node (ref "R11") (pin "2") (pinfunction "2_2") (pintype "passive"))
    )
    (net (code "45") (name "/M2_VB1") (class "Default")
      (node (ref "C20") (pin "2") (pinfunction "2_2") (pintype "passive"))
      (node (ref "D4") (pin "1") (pinfunction "K_1") (pintype "passive"))
      (node (ref "U7") (pin "20") (pinfunction "VB1_20") (pintype "passive"))
    )
    (net (code "46") (name "/M2_VB2") (class "Default")
      (node (ref "C21") (pin "2") (pinfunction "2_2") (pintype "passive"))
      (node (ref "D5") (pin "1") (pinfunction "K_1") (pintype "passive"))
      (node (ref "U7") (pin "17") (pinfunction "VB2_17") (pintype "passive"))
    )
    (net (code "47") (name "/M2_VB3") (class "Default")
      (node (ref "C22") (pin "2") (pinfunction "2_2") (pintype "passive"))
      (node (ref "D6") (pin "1") (pinfunction "K_1") (pintype "passive"))
      (node (ref "U7") (pin "14") (pinfunction "VB3_14") (pintype "passive"))
    )
    (net (code "48") (name "/M2_VS1") (class "Default")
      (node (ref "C20") (pin "1") (pinfunction "1_1") (pintype "passive"))
      (node (ref "P21") (pin "1") (pinfunction "1_1") (pintype "passive"))
      (node (ref "Q8") (pin "10") (pinfunction "S1/D2_10") (pintype "passive"))
      (node (ref "R28") (pin "2") (pinfunction "2_2") (pintype "passive"))
      (node (ref "U7") (pin "18") (pinfunction "VS1_18") (pintype "passive"))
    )
    (net (code "49") (name "/M2_VS2") (class "Default")
      (node (ref "C21") (pin "1") (pinfunction "1_1") (pintype "passive"))
      (node (ref "P16") (pin "1") (pinfunction "1_1") (pintype "passive"))
      (node (ref "Q3") (pin "10") (pinfunction "S1/D2_10") (pintype "passive"))
      (node (ref "R36") (pin "2") (pinfunction "2_2") (pintype "passive"))
      (node (ref "U7") (pin "15") (pinfunction "VS2_15") (pintype "passive"))
    )
    (net (code "50") (name "/M2_VS3") (class "Default")
      (node (ref "C22") (pin "1") (pinfunction "1_1") (pintype "passive"))
      (node (ref "P22") (pin "1") (pinfunction "1_1") (pintype "passive"))
      (node (ref "Q9") (pin "10") (pinfunction "S1/D2_10") (pintype "passive"))
      (node (ref "R44") (pin "2") (pinfunction "2_2") (pintype "passive"))
      (node (ref "U7") (pin "12") (pinfunction "VS3_12") (pintype "passive"))
    )
    (net (code "51") (name "/M3_AIN") (class "Default")
      (node (ref "R20") (pin "2") (pinfunction "2_2") (pintype "passive"))
      (node (ref "R30") (pin "1") (pinfunction "1_1") (pintype "passive"))
      (node (ref "R31") (pin "2") (pinfunction "2_2") (pintype "passive"))
      (node (ref "U4") (pin "2") (pinfunction "P0.0_2") (pintype "passive"))
    )
    (net (code "52") (name "/M3_BIN") (class "Default")
      (node (ref "R21") (pin "2") (pinfunction "2_2") (pintype "passive"))
      (node (ref "R38") (pin "1") (pinfunction "1_1") (pintype "passive"))
      (node (ref "R39") (pin "2") (pinfunction "2_2") (pintype "passive"))
      (node (ref "U4") (pin "20") (pinfunction "P0.2_20") (pintype "passive"))
    )
    (net (code "53") (name "/M3_C") (class "Default")
      (node (ref "R20") (pin "1") (pinfunction "1_1") (pintype "passive"))
      (node (ref "R21") (pin "1") (pinfunction "1_1") (pintype "passive"))
      (node (ref "R22") (pin "1") (pinfunction "1_1") (pintype "passive"))
      (node (ref "U4") (pin "19") (pinfunction "P0.3_19") (pintype "passive"))
    )
    (net (code "54") (name "/M3_C2CK") (class "Default")
      (node (ref "P6") (pin "1") (pinfunction "1_1") (pintype "passive"))
      (node (ref "R8") (pin "2") (pinfunction "2_2") (pintype "passive"))
      (node (ref "U4") (pin "5") (pinfunction "RSTB/C2CK_5") (pintype "passive"))
    )
    (net (code "55") (name "/M3_C2D") (class "Default")
      (node (ref "P7") (pin "1") (pinfunction "1_1") (pintype "passive"))
      (node (ref "U4") (pin "6") (pinfunction "P2.0/C2D_6") (pintype "passive"))
    )
    (net (code "56") (name "/M3_CIN") (class "Default")
      (node (ref "R22") (pin "2") (pinfunction "2_2") (pintype "passive"))
      (node (ref "R46") (pin "1") (pinfunction "1_1") (pintype "passive"))
      (node (ref "R47") (pin "2") (pinfunction "2_2") (pintype "passive"))
      (node (ref "U4") (pin "1") (pinfunction "P0.1_1") (pintype "passive"))
    )
    (net (code "57") (name "/M3_HIN1") (class "Default")
      (node (ref "U4") (pin "14") (pinfunction "P1.0_14") (pintype "passive"))
      (node (ref "U8") (pin "22") (pinfunction "HIN1_22") (pintype "passive"))
    )
    (net (code "58") (name "/M3_HIN2") (class "Default")
      (node (ref "U4") (pin "13") (pinfunction "P1.1_13") (pintype "passive"))
      (node (ref "U8") (pin "23") (pinfunction "HIN2_23") (pintype "passive"))
    )
    (net (code "59") (name "/M3_HIN3") (class "Default")
      (node (ref "U4") (pin "11") (pinfunction "P1.2_11") (pintype "passive"))
      (node (ref "U8") (pin "24") (pinfunction "HIN3_24") (pintype "passive"))
    )
    (net (code "60") (name "/M3_HO1") (class "Default")
      (node (ref "R53") (pin "2") (pinfunction "2_2") (pintype "passive"))
      (node (ref "U8") (pin "19") (pinfunction "HO1_19") (pintype "passive"))
    )
    (net (code "61") (name "/M3_HO2") (class "Default")
      (node (ref "R65") (pin "2") (pinfunction "2_2") (pintype "passive"))
      (node (ref "U8") (pin "16") (pinfunction "HO2_16") (pintype "passive"))
    )
    (net (code "62") (name "/M3_HO3") (class "Default")
      (node (ref "R54") (pin "2") (pinfunction "2_2") (pintype "passive"))
      (node (ref "U8") (pin "13") (pinfunction "HO3_13") (pintype "passive"))
    )
    (net (code "63") (name "/M3_LIN1") (class "Default")
      (node (ref "U4") (pin "10") (pinfunction "P1.3_10") (pintype "passive"))
      (node (ref "U8") (pin "1") (pinfunction "LIN1_1") (pintype "passive"))
    )
    (net (code "64") (name "/M3_LIN2") (class "Default")
      (node (ref "U4") (pin "9") (pinfunction "P1.4_9") (pintype "passive"))
      (node (ref "U8") (pin "2") (pinfunction "LIN2_2") (pintype "passive"))
    )
    (net (code "65") (name "/M3_LIN3") (class "Default")
      (node (ref "U4") (pin "8") (pinfunction "P1.5_8") (pintype "passive"))
      (node (ref "U8") (pin "3") (pinfunction "LIN3_3") (pintype "passive"))
    )
    (net (code "66") (name "/M3_LO1") (class "Default")
      (node (ref "R59") (pin "2") (pinfunction "2_2") (pintype "passive"))
      (node (ref "U8") (pin "11") (pinfunction "LO1_11") (pintype "passive"))
    )
    (net (code "67") (name "/M3_LO2") (class "Default")
      (node (ref "R71") (pin "2") (pinfunction "2_2") (pintype "passive"))
      (node (ref "U8") (pin "10") (pinfunction "LO2_10") (pintype "passive"))
    )
    (net (code "68") (name "/M3_LO3") (class "Default")
      (node (ref "R60") (pin "2") (pinfunction "2_2") (pintype "passive"))
      (node (ref "U8") (pin "9") (pinfunction "LO3_9") (pintype "passive"))
    )
    (net (code "69") (name "/M3_PWM") (class "Default")
      (node (ref "R12") (pin "2") (pinfunction "2_2") (pintype "passive"))
    )
    (net (code "70") (name "/M3_VB1") (class "Default")
      (node (ref "C23") (pin "2") (pinfunction "2_2") (pintype "passive"))
      (node (ref "D7") (pin "1") (pinfunction "K_1") (pintype "passive"))
      (node (ref "U8") (pin "20") (pinfunction "VB1_20") (pintype "passive"))
    )
    (net (code "71") (name "/M3_VB2") (class "Default")
      (node (ref "C24") (pin "2") (pinfunction "2_2") (pintype "passive"))
      (node (ref "D8") (pin "1") (pinfunction "K_1") (pintype "passive"))
      (node (ref "U8") (pin "17") (pinfunction "VB2_17") (pintype "passive"))
    )
    (net (code "72") (name "/M3_VB3") (class "Default")
      (node (ref "C25") (pin "2") (pinfunction "2_2") (pintype "passive"))
      (node (ref "D9") (pin "1") (pinfunction "K_1") (pintype "passive"))
      (node (ref "U8") (pin "14") (pinfunction "VB3_14") (pintype "passive"))
    )
    (net (code "73") (name "/M3_VS1") (class "Default")
      (node (ref "C23") (pin "1") (pinfunction "1_1") (pintype "passive"))
      (node (ref "P17") (pin "1") (pinfunction "1_1") (pintype "passive"))
      (node (ref "Q4") (pin "10") (pinfunction "S1/D2_10") (pintype "passive"))
      (node (ref "R30") (pin "2") (pinfunction "2_2") (pintype "passive"))
      (node (ref "U8") (pin "18") (pinfunction "VS1_18") (pintype "passive"))
    )
    (net (code "74") (name "/M3_VS2") (class "Default")
      (node (ref "C24") (pin "1") (pinfunction "1_1") (pintype "passive"))
      (node (ref "P23") (pin "1") (pinfunction "1_1") (pintype "passive"))
      (node (ref "Q10") (pin "10") (pinfunction "S1/D2_10") (pintype "passive"))
      (node (ref "R38") (pin "2") (pinfunction "2_2") (pintype "passive"))
      (node (ref "U8") (pin "15") (pinfunction "VS2_15") (pintype "passive"))
    )
    (net (code "75") (name "/M3_VS3") (class "Default")
      (node (ref "C25") (pin "1") (pinfunction "1_1") (pintype "passive"))
      (node (ref "P18") (pin "1") (pinfunction "1_1") (pintype "passive"))
      (node (ref "Q5") (pin "10") (pinfunction "S1/D2_10") (pintype "passive"))
      (node (ref "R46") (pin "2") (pinfunction "2_2") (pintype "passive"))
      (node (ref "U8") (pin "12") (pinfunction "VS3_12") (pintype "passive"))
    )
    (net (code "76") (name "/M4_AIN") (class "Default")
      (node (ref "R23") (pin "2") (pinfunction "2_2") (pintype "passive"))
      (node (ref "R32") (pin "1") (pinfunction "1_1") (pintype "passive"))
      (node (ref "R33") (pin "2") (pinfunction "2_2") (pintype "passive"))
      (node (ref "U5") (pin "2") (pinfunction "P0.0_2") (pintype "passive"))
    )
    (net (code "77") (name "/M4_BIN") (class "Default")
      (node (ref "R24") (pin "2") (pinfunction "2_2") (pintype "passive"))
      (node (ref "R40") (pin "1") (pinfunction "1_1") (pintype "passive"))
      (node (ref "R41") (pin "2") (pinfunction "2_2") (pintype "passive"))
      (node (ref "U5") (pin "20") (pinfunction "P0.2_20") (pintype "passive"))
    )
    (net (code "78") (name "/M4_C") (class "Default")
      (node (ref "R23") (pin "1") (pinfunction "1_1") (pintype "passive"))
      (node (ref "R24") (pin "1") (pinfunction "1_1") (pintype "passive"))
      (node (ref "R25") (pin "1") (pinfunction "1_1") (pintype "passive"))
      (node (ref "U5") (pin "19") (pinfunction "P0.3_19") (pintype "passive"))
    )
    (net (code "79") (name "/M4_C2CK") (class "Default")
      (node (ref "P8") (pin "1") (pinfunction "1_1") (pintype "passive"))
      (node (ref "R9") (pin "2") (pinfunction "2_2") (pintype "passive"))
      (node (ref "U5") (pin "5") (pinfunction "RSTB/C2CK_5") (pintype "passive"))
    )
    (net (code "80") (name "/M4_C2D") (class "Default")
      (node (ref "P9") (pin "1") (pinfunction "1_1") (pintype "passive"))
      (node (ref "U5") (pin "6") (pinfunction "P2.0/C2D_6") (pintype "passive"))
    )
    (net (code "81") (name "/M4_CIN") (class "Default")
      (node (ref "R25") (pin "2") (pinfunction "2_2") (pintype "passive"))
      (node (ref "R48") (pin "1") (pinfunction "1_1") (pintype "passive"))
      (node (ref "R49") (pin "2") (pinfunction "2_2") (pintype "passive"))
      (node (ref "U5") (pin "1") (pinfunction "P0.1_1") (pintype "passive"))
    )
    (net (code "82") (name "/M4_HIN1") (class "Default")
      (node (ref "U5") (pin "14") (pinfunction "P1.0_14") (pintype "passive"))
      (node (ref "U9") (pin "22") (pinfunction "HIN1_22") (pintype "passive"))
    )
    (net (code "83") (name "/M4_HIN2") (class "Default")
      (node (ref "U5") (pin "13") (pinfunction "P1.1_13") (pintype "passive"))
      (node (ref "U9") (pin "23") (pinfunction "HIN2_23") (pintype "passive"))
    )
    (net (code "84") (name "/M4_HIN3") (class "Default")
      (node (ref "U5") (pin "11") (pinfunction "P1.2_11") (pintype "passive"))
      (node (ref "U9") (pin "24") (pinfunction "HIN3_24") (pintype "passive"))
    )
    (net (code "85") (name "/M4_HO1") (class "Default")
      (node (ref "R66") (pin "2") (pinfunction "2_2") (pintype "passive"))
      (node (ref "U9") (pin "19") (pinfunction "HO1_19") (pintype "passive"))
    )
    (net (code "86") (name "/M4_HO2") (class "Default")
      (node (ref "R55") (pin "2") (pinfunction "2_2") (pintype "passive"))
      (node (ref "U9") (pin "16") (pinfunction "HO2_16") (pintype "passive"))
    )
    (net (code "87") (name "/M4_HO3") (class "Default")
      (node (ref "R67") (pin "2") (pinfunction "2_2") (pintype "passive"))
      (node (ref "U9") (pin "13") (pinfunction "HO3_13") (pintype "passive"))
    )
    (net (code "88") (name "/M4_LIN1") (class "Default")
      (node (ref "U5") (pin "10") (pinfunction "P1.3_10") (pintype "passive"))
      (node (ref "U9") (pin "1") (pinfunction "LIN1_1") (pintype "passive"))
    )
    (net (code "89") (name "/M4_LIN2") (class "Default")
      (node (ref "U5") (pin "9") (pinfunction "P1.4_9") (pintype "passive"))
      (node (ref "U9") (pin "2") (pinfunction "LIN2_2") (pintype "passive"))
    )
    (net (code "90") (name "/M4_LIN3") (class "Default")
      (node (ref "U5") (pin "8") (pinfunction "P1.5_8") (pintype "passive"))
      (node (ref "U9") (pin "3") (pinfunction "LIN3_3") (pintype "passive"))
    )
    (net (code "91") (name "/M4_LO1") (class "Default")
      (node (ref "R72") (pin "2") (pinfunction "2_2") (pintype "passive"))
      (node (ref "U9") (pin "11") (pinfunction "LO1_11") (pintype "passive"))
    )
    (net (code "92") (name "/M4_LO2") (class "Default")
      (node (ref "R61") (pin "2") (pinfunction "2_2") (pintype "passive"))
      (node (ref "U9") (pin "10") (pinfunction "LO2_10") (pintype "passive"))
    )
    (net (code "93") (name "/M4_LO3") (class "Default")
      (node (ref "R73") (pin "2") (pinfunction "2_2") (pintype "passive"))
      (node (ref "U9") (pin "9") (pinfunction "LO3_9") (pintype "passive"))
    )
    (net (code "94") (name "/M4_PWM") (class "Default")
      (node (ref "R13") (pin "2") (pinfunction "2_2") (pintype "passive"))
    )
    (net (code "95") (name "/M4_VB1") (class "Default")
      (node (ref "C26") (pin "2") (pinfunction "2_2") (pintype "passive"))
      (node (ref "D10") (pin "1") (pinfunction "K_1") (pintype "passive"))
      (node (ref "U9") (pin "20") (pinfunction "VB1_20") (pintype "passive"))
    )
    (net (code "96") (name "/M4_VB2") (class "Default")
      (node (ref "C27") (pin "2") (pinfunction "2_2") (pintype "passive"))
      (node (ref "D11") (pin "1") (pinfunction "K_1") (pintype "passive"))
      (node (ref "U9") (pin "17") (pinfunction "VB2_17") (pintype "passive"))
    )
    (net (code "97") (name "/M4_VB3") (class "Default")
      (node (ref "C28") (pin "2") (pinfunction "2_2") (pintype "passive"))
      (node (ref "D12") (pin "1") (pinfunction "K_1") (pintype "passive"))
      (node (ref "U9") (pin "14") (pinfunction "VB3_14") (pintype "passive"))
    )
    (net (code "98") (name "/M4_VS1") (class "Default")
      (node (ref "C26") (pin "1") (pinfunction "1_1") (pintype "passive"))
      (node (ref "P24") (pin "1") (pinfunction "1_1") (pintype "passive"))
      (node (ref "Q11") (pin "10") (pinfunction "S1/D2_10") (pintype "passive"))
      (node (ref "R32") (pin "2") (pinfunction "2_2") (pintype "passive"))
      (node (ref "U9") (pin "18") (pinfunction "VS1_18") (pintype "passive"))
    )
    (net (code "99") (name "/M4_VS2") (class "Default")
      (node (ref "C27") (pin "1") (pinfunction "1_1") (pintype "passive"))
      (node (ref "P19") (pin "1") (pinfunction "1_1") (pintype "passive"))
      (node (ref "Q6") (pin "10") (pinfunction "S1/D2_10") (pintype "passive"))
      (node (ref "R40") (pin "2") (pinfunction "2_2") (pintype "passive"))
      (node (ref "U9") (pin "15") (pinfunction "VS2_15") (pintype "passive"))
    )
    (net (code "100") (name "/M4_VS3") (class "Default")
      (node (ref "C28") (pin "1") (pinfunction "1_1") (pintype "passive"))
      (node (ref "P25") (pin "1") (pinfunction "1_1") (pintype "passive"))
      (node (ref "Q12") (pin "10") (pinfunction "S1/D2_10") (pintype "passive"))
      (node (ref "R48") (pin "2") (pinfunction "2_2") (pintype "passive"))
      (node (ref "U9") (pin "12") (pinfunction "VS3_12") (pintype "passive"))
    )
    (net (code "101") (name "9V") (class "Default")
      (node (ref "C13") (pin "2") (pinfunction "2_2") (pintype "passive"))
      (node (ref "C14") (pin "2") (pinfunction "2_2") (pintype "passive"))
      (node (ref "C15") (pin "2") (pinfunction "2_2") (pintype "passive"))
      (node (ref "C16") (pin "2") (pinfunction "2_2") (pintype "passive"))
      (node (ref "D1") (pin "2") (pinfunction "A_2") (pintype "passive"))
      (node (ref "D10") (pin "2") (pinfunction "A_2") (pintype "passive"))
      (node (ref "D11") (pin "2") (pinfunction "A_2") (pintype "passive"))
      (node (ref "D12") (pin "2") (pinfunction "A_2") (pintype "passive"))
      (node (ref "D2") (pin "2") (pinfunction "A_2") (pintype "passive"))
      (node (ref "D3") (pin "2") (pinfunction "A_2") (pintype "passive"))
      (node (ref "D4") (pin "2") (pinfunction "A_2") (pintype "passive"))
      (node (ref "D5") (pin "2") (pinfunction "A_2") (pintype "passive"))
      (node (ref "D6") (pin "2") (pinfunction "A_2") (pintype "passive"))
      (node (ref "D7") (pin "2") (pinfunction "A_2") (pintype "passive"))
      (node (ref "D8") (pin "2") (pinfunction "A_2") (pintype "passive"))
      (node (ref "D9") (pin "2") (pinfunction "A_2") (pintype "passive"))
      (node (ref "U6") (pin "4") (pinfunction "VCC_4") (pintype "passive"))
      (node (ref "U7") (pin "4") (pinfunction "VCC_4") (pintype "passive"))
      (node (ref "U8") (pin "4") (pinfunction "VCC_4") (pintype "passive"))
      (node (ref "U9") (pin "4") (pinfunction "VCC_4") (pintype "passive"))
    )
    (net (code "102") (name "GND") (class "Default")
      (node (ref "C10") (pin "2") (pinfunction "2_2") (pintype "passive"))
      (node (ref "C11") (pin "2") (pinfunction "2_2") (pintype "passive"))
      (node (ref "C12") (pin "2") (pinfunction "2_2") (pintype "passive"))
      (node (ref "C13") (pin "1") (pinfunction "1_1") (pintype "passive"))
      (node (ref "C14") (pin "1") (pinfunction "1_1") (pintype "passive"))
      (node (ref "C15") (pin "1") (pinfunction "1_1") (pintype "passive"))
      (node (ref "C16") (pin "1") (pinfunction "1_1") (pintype "passive"))
      (node (ref "C9") (pin "2") (pinfunction "2_2") (pintype "passive"))
      (node (ref "Q1") (pin "5") (pinfunction "S2_5") (pintype "passive"))
      (node (ref "Q1") (pin "6") (pinfunction "S2_6") (pintype "passive"))
      (node (ref "Q1") (pin "7") (pinfunction "S2_7") (pintype "passive"))
      (node (ref "Q10") (pin "5") (pinfunction "S2_5") (pintype "passive"))
      (node (ref "Q10") (pin "6") (pinfunction "S2_6") (pintype "passive"))
      (node (ref "Q10") (pin "7") (pinfunction "S2_7") (pintype "passive"))
      (node (ref "Q11") (pin "5") (pinfunction "S2_5") (pintype "passive"))
      (node (ref "Q11") (pin "6") (pinfunction "S2_6") (pintype "passive"))
      (node (ref "Q11") (pin "7") (pinfunction "S2_7") (pintype "passive"))
      (node (ref "Q12") (pin "5") (pinfunction "S2_5") (pintype "passive"))
      (node (ref "Q12") (pin "6") (pinfunction "S2_6") (pintype "passive"))
      (node (ref "Q12") (pin "7") (pinfunction "S2_7") (pintype "passive"))
      (node (ref "Q2") (pin "5") (pinfunction "S2_5") (pintype "passive"))
      (node (ref "Q2") (pin "6") (pinfunction "S2_6") (pintype "passive"))
      (node (ref "Q2") (pin "7") (pinfunction "S2_7") (pintype "passive"))
      (node (ref "Q3") (pin "5") (pinfunction "S2_5") (pintype "passive"))
      (node (ref "Q3") (pin "6") (pinfunction "S2_6") (pintype "passive"))
      (node (ref "Q3") (pin "7") (pinfunction "S2_7") (pintype "passive"))
      (node (ref "Q4") (pin "5") (pinfunction "S2_5") (pintype "passive"))
      (node (ref "Q4") (pin "6") (pinfunction "S2_6") (pintype "passive"))
      (node (ref "Q4") (pin "7") (pinfunction "S2_7") (pintype "passive"))
      (node (ref "Q5") (pin "5") (pinfunction "S2_5") (pintype "passive"))
      (node (ref "Q5") (pin "6") (pinfunction "S2_6") (pintype "passive"))
      (node (ref "Q5") (pin "7") (pinfunction "S2_7") (pintype "passive"))
      (node (ref "Q6") (pin "5") (pinfunction "S2_5") (pintype "passive"))
      (node (ref "Q6") (pin "6") (pinfunction "S2_6") (pintype "passive"))
      (node (ref "Q6") (pin "7") (pinfunction "S2_7") (pintype "passive"))
      (node (ref "Q7") (pin "5") (pinfunction "S2_5") (pintype "passive"))
      (node (ref "Q7") (pin "6") (pinfunction "S2_6") (pintype "passive"))
      (node (ref "Q7") (pin "7") (pinfunction "S2_7") (pintype "passive"))
      (node (ref "Q8") (pin "5") (pinfunction "S2_5") (pintype "passive"))
      (node (ref "Q8") (pin "6") (pinfunction "S2_6") (pintype "passive"))
      (node (ref "Q8") (pin "7") (pinfunction "S2_7") (pintype "passive"))
      (node (ref "Q9") (pin "5") (pinfunction "S2_5") (pintype "passive"))
      (node (ref "Q9") (pin "6") (pinfunction "S2_6") (pintype "passive"))
      (node (ref "Q9") (pin "7") (pinfunction "S2_7") (pintype "passive"))
      (node (ref "R27") (pin "1") (pinfunction "1_1") (pintype "passive"))
      (node (ref "R29") (pin "1") (pinfunction "1_1") (pintype "passive"))
      (node (ref "R31") (pin "1") (pinfunction "1_1") (pintype "passive"))
      (node (ref "R33") (pin "1") (pinfunction "1_1") (pintype "passive"))
      (node (ref "R35") (pin "1") (pinfunction "1_1") (pintype "passive"))
      (node (ref "R37") (pin "1") (pinfunction "1_1") (pintype "passive"))
      (node (ref "R39") (pin "1") (pinfunction "1_1") (pintype "passive"))
      (node (ref "R41") (pin "1") (pinfunction "1_1") (pintype "passive"))
      (node (ref "R43") (pin "1") (pinfunction "1_1") (pintype "passive"))
      (node (ref "R45") (pin "1") (pinfunction "1_1") (pintype "passive"))
      (node (ref "R47") (pin "1") (pinfunction "1_1") (pintype "passive"))
      (node (ref "R49") (pin "1") (pinfunction "1_1") (pintype "passive"))
      (node (ref "U2") (pin "12") (pinfunction "GND_12") (pintype "passive"))
      (node (ref "U2") (pin "21") (pinfunction "GND_21") (pintype "passive"))
      (node (ref "U2") (pin "3") (pinfunction "GND_3") (pintype "passive"))
      (node (ref "U3") (pin "12") (pinfunction "GND_12") (pintype "passive"))
      (node (ref "U3") (pin "21") (pinfunction "GND_21") (pintype "passive"))
      (node (ref "U3") (pin "3") (pinfunction "GND_3") (pintype "passive"))
      (node (ref "U4") (pin "12") (pinfunction "GND_12") (pintype "passive"))
      (node (ref "U4") (pin "21") (pinfunction "GND_21") (pintype "passive"))
      (node (ref "U4") (pin "3") (pinfunction "GND_3") (pintype "passive"))
      (node (ref "U5") (pin "12") (pinfunction "GND_12") (pintype "passive"))
      (node (ref "U5") (pin "21") (pinfunction "GND_21") (pintype "passive"))
      (node (ref "U5") (pin "3") (pinfunction "GND_3") (pintype "passive"))
      (node (ref "U6") (pin "25") (pinfunction "EP_25") (pintype "passive"))
      (node (ref "U6") (pin "6") (pinfunction "COM_6") (pintype "passive"))
      (node (ref "U7") (pin "25") (pinfunction "EP_25") (pintype "passive"))
      (node (ref "U7") (pin "6") (pinfunction "COM_6") (pintype "passive"))
      (node (ref "U8") (pin "25") (pinfunction "EP_25") (pintype "passive"))
      (node (ref "U8") (pin "6") (pinfunction "COM_6") (pintype "passive"))
      (node (ref "U9") (pin "25") (pinfunction "EP_25") (pintype "passive"))
      (node (ref "U9") (pin "6") (pinfunction "COM_6") (pintype "passive"))
    )
    (net (code "103") (name "Net-(Q1-G1)") (class "Default")
      (node (ref "Q1") (pin "1") (pinfunction "G1_1") (pintype "passive"))
      (node (ref "R50") (pin "1") (pinfunction "1_1") (pintype "passive"))
    )
    (net (code "104") (name "Net-(Q1-G2)") (class "Default")
      (node (ref "Q1") (pin "8") (pinfunction "G2_8") (pintype "passive"))
      (node (ref "R56") (pin "1") (pinfunction "1_1") (pintype "passive"))
    )
    (net (code "105") (name "Net-(Q2-G1)") (class "Default")
      (node (ref "Q2") (pin "1") (pinfunction "G1_1") (pintype "passive"))
      (node (ref "R51") (pin "1") (pinfunction "1_1") (pintype "passive"))
    )
    (net (code "106") (name "Net-(Q2-G2)") (class "Default")
      (node (ref "Q2") (pin "8") (pinfunction "G2_8") (pintype "passive"))
      (node (ref "R57") (pin "1") (pinfunction "1_1") (pintype "passive"))
    )
    (net (code "107") (name "Net-(Q3-G1)") (class "Default")
      (node (ref "Q3") (pin "1") (pinfunction "G1_1") (pintype "passive"))
      (node (ref "R52") (pin "1") (pinfunction "1_1") (pintype "passive"))
    )
    (net (code "108") (name "Net-(Q3-G2)") (class "Default")
      (node (ref "Q3") (pin "8") (pinfunction "G2_8") (pintype "passive"))
      (node (ref "R58") (pin "1") (pinfunction "1_1") (pintype "passive"))
    )
    (net (code "109") (name "Net-(Q4-G1)") (class "Default")
      (node (ref "Q4") (pin "1") (pinfunction "G1_1") (pintype "passive"))
      (node (ref "R53") (pin "1") (pinfunction "1_1") (pintype "passive"))
    )
    (net (code "110") (name "Net-(Q4-G2)") (class "Default")
      (node (ref "Q4") (pin "8") (pinfunction "G2_8") (pintype "passive"))
      (node (ref "R59") (pin "1") (pinfunction "1_1") (pintype "passive"))
    )
    (net (code "111") (name "Net-(Q5-G1)") (class "Default")
      (node (ref "Q5") (pin "1") (pinfunction "G1_1") (pintype "passive"))
      (node (ref "R54") (pin "1") (pinfunction "1_1") (pintype "passive"))
    )
    (net (code "112") (name "Net-(Q5-G2)") (class "Default")
      (node (ref "Q5") (pin "8") (pinfunction "G2_8") (pintype "passive"))
      (node (ref "R60") (pin "1") (pinfunction "1_1") (pintype "passive"))
    )
    (net (code "113") (name "Net-(Q6-G1)") (class "Default")
      (node (ref "Q6") (pin "1") (pinfunction "G1_1") (pintype "passive"))
      (node (ref "R55") (pin "1") (pinfunction "1_1") (pintype "passive"))
    )
    (net (code "114") (name "Net-(Q6-G2)") (class "Default")
      (node (ref "Q6") (pin "8") (pinfunction "G2_8") (pintype "passive"))
      (node (ref "R61") (pin "1") (pinfunction "1_1") (pintype "passive"))
    )
    (net (code "115") (name "Net-(Q7-G1)") (class "Default")
      (node (ref "Q7") (pin "1") (pinfunction "G1_1") (pintype "passive"))
      (node (ref "R62") (pin "1") (pinfunction "1_1") (pintype "passive"))
    )
    (net (code "116") (name "Net-(Q7-G2)") (class "Default")
      (node (ref "Q7") (pin "8") (pinfunction "G2_8") (pintype "passive"))
      (node (ref "R68") (pin "1") (pinfunction "1_1") (pintype "passive"))
    )
    (net (code "117") (name "Net-(Q8-G1)") (class "Default")
      (node (ref "Q8") (pin "1") (pinfunction "G1_1") (pintype "passive"))
      (node (ref "R63") (pin "1") (pinfunction "1_1") (pintype "passive"))
    )
    (net (code "118") (name "Net-(Q8-G2)") (class "Default")
      (node (ref "Q8") (pin "8") (pinfunction "G2_8") (pintype "passive"))
      (node (ref "R69") (pin "1") (pinfunction "1_1") (pintype "passive"))
    )
    (net (code "119") (name "Net-(Q9-G1)") (class "Default")
      (node (ref "Q9") (pin "1") (pinfunction "G1_1") (pintype "passive"))
      (node (ref "R64") (pin "1") (pinfunction "1_1") (pintype "passive"))
    )
    (net (code "120") (name "Net-(Q9-G2)") (class "Default")
      (node (ref "Q9") (pin "8") (pinfunction "G2_8") (pintype "passive"))
      (node (ref "R70") (pin "1") (pinfunction "1_1") (pintype "passive"))
    )
    (net (code "121") (name "Net-(Q10-G1)") (class "Default")
      (node (ref "Q10") (pin "1") (pinfunction "G1_1") (pintype "passive"))
      (node (ref "R65") (pin "1") (pinfunction "1_1") (pintype "passive"))
    )
    (net (code "122") (name "Net-(Q10-G2)") (class "Default")
      (node (ref "Q10") (pin "8") (pinfunction "G2_8") (pintype "passive"))
      (node (ref "R71") (pin "1") (pinfunction "1_1") (pintype "passive"))
    )
    (net (code "123") (name "Net-(Q11-G1)") (class "Default")
      (node (ref "Q11") (pin "1") (pinfunction "G1_1") (pintype "passive"))
      (node (ref "R66") (pin "1") (pinfunction "1_1") (pintype "passive"))
    )
    (net (code "124") (name "Net-(Q11-G2)") (class "Default")
      (node (ref "Q11") (pin "8") (pinfunction "G2_8") (pintype "passive"))
      (node (ref "R72") (pin "1") (pinfunction "1_1") (pintype "passive"))
    )
    (net (code "125") (name "Net-(Q12-G1)") (class "Default")
      (node (ref "Q12") (pin "1") (pinfunction "G1_1") (pintype "passive"))
      (node (ref "R67") (pin "1") (pinfunction "1_1") (pintype "passive"))
    )
    (net (code "126") (name "Net-(Q12-G2)") (class "Default")
      (node (ref "Q12") (pin "8") (pinfunction "G2_8") (pintype "passive"))
      (node (ref "R73") (pin "1") (pinfunction "1_1") (pintype "passive"))
    )
    (net (code "127") (name "Net-(U2-P0.4)") (class "Default")
      (node (ref "R10") (pin "1") (pinfunction "1_1") (pintype "passive"))
      (node (ref "U2") (pin "18") (pinfunction "P0.4_18") (pintype "passive"))
    )
    (net (code "128") (name "Net-(U3-P0.4)") (class "Default")
      (node (ref "R11") (pin "1") (pinfunction "1_1") (pintype "passive"))
      (node (ref "U3") (pin "18") (pinfunction "P0.4_18") (pintype "passive"))
    )
    (net (code "129") (name "Net-(U4-P0.4)") (class "Default")
      (node (ref "R12") (pin "1") (pinfunction "1_1") (pintype "passive"))
      (node (ref "U4") (pin "18") (pinfunction "P0.4_18") (pintype "passive"))
    )
    (net (code "130") (name "Net-(U5-P0.4)") (class "Default")
      (node (ref "R13") (pin "1") (pinfunction "1_1") (pintype "passive"))
      (node (ref "U5") (pin "18") (pinfunction "P0.4_18") (pintype "passive"))
    )
    (net (code "131") (name "Peripheral_3.3V") (class "Default")
      (node (ref "C10") (pin "1") (pinfunction "1_1") (pintype "passive"))
      (node (ref "C11") (pin "1") (pinfunction "1_1") (pintype "passive"))
      (node (ref "C12") (pin "1") (pinfunction "1_1") (pintype "passive"))
      (node (ref "C9") (pin "1") (pinfunction "1_1") (pintype "passive"))
      (node (ref "R6") (pin "1") (pinfunction "1_1") (pintype "passive"))
      (node (ref "R7") (pin "1") (pinfunction "1_1") (pintype "passive"))
      (node (ref "R8") (pin "1") (pinfunction "1_1") (pintype "passive"))
      (node (ref "R9") (pin "1") (pinfunction "1_1") (pintype "passive"))
      (node (ref "U2") (pin "4") (pinfunction "VDD_4") (pintype "passive"))
      (node (ref "U3") (pin "4") (pinfunction "VDD_4") (pintype "passive"))
      (node (ref "U4") (pin "4") (pinfunction "VDD_4") (pintype "passive"))
      (node (ref "U5") (pin "4") (pinfunction "VDD_4") (pintype "passive"))
    )
    (net (code "132") (name "VBAT") (class "Default")
      (node (ref "Q1") (pin "2") (pinfunction "D1_2") (pintype "passive"))
      (node (ref "Q1") (pin "3") (pinfunction "D1_3") (pintype "passive"))
      (node (ref "Q1") (pin "4") (pinfunction "D1_4") (pintype "passive"))
      (node (ref "Q1") (pin "9") (pinfunction "D1_9") (pintype "passive"))
      (node (ref "Q10") (pin "2") (pinfunction "D1_2") (pintype "passive"))
      (node (ref "Q10") (pin "3") (pinfunction "D1_3") (pintype "passive"))
      (node (ref "Q10") (pin "4") (pinfunction "D1_4") (pintype "passive"))
      (node (ref "Q10") (pin "9") (pinfunction "D1_9") (pintype "passive"))
      (node (ref "Q11") (pin "2") (pinfunction "D1_2") (pintype "passive"))
      (node (ref "Q11") (pin "3") (pinfunction "D1_3") (pintype "passive"))
      (node (ref "Q11") (pin "4") (pinfunction "D1_4") (pintype "passive"))
      (node (ref "Q11") (pin "9") (pinfunction "D1_9") (pintype "passive"))
      (node (ref "Q12") (pin "2") (pinfunction "D1_2") (pintype "passive"))
      (node (ref "Q12") (pin "3") (pinfunction "D1_3") (pintype "passive"))
      (node (ref "Q12") (pin "4") (pinfunction "D1_4") (pintype "passive"))
      (node (ref "Q12") (pin "9") (pinfunction "D1_9") (pintype "passive"))
      (node (ref "Q2") (pin "2") (pinfunction "D1_2") (pintype "passive"))
      (node (ref "Q2") (pin "3") (pinfunction "D1_3") (pintype "passive"))
      (node (ref "Q2") (pin "4") (pinfunction "D1_4") (pintype "passive"))
      (node (ref "Q2") (pin "9") (pinfunction "D1_9") (pintype "passive"))
      (node (ref "Q3") (pin "2") (pinfunction "D1_2") (pintype "passive"))
      (node (ref "Q3") (pin "3") (pinfunction "D1_3") (pintype "passive"))
      (node (ref "Q3") (pin "4") (pinfunction "D1_4") (pintype "passive"))
      (node (ref "Q3") (pin "9") (pinfunction "D1_9") (pintype "passive"))
      (node (ref "Q4") (pin "2") (pinfunction "D1_2") (pintype "passive"))
      (node (ref "Q4") (pin "3") (pinfunction "D1_3") (pintype "passive"))
      (node (ref "Q4") (pin "4") (pinfunction "D1_4") (pintype "passive"))
      (node (ref "Q4") (pin "9") (pinfunction "D1_9") (pintype "passive"))
      (node (ref "Q5") (pin "2") (pinfunction "D1_2") (pintype "passive"))
      (node (ref "Q5") (pin "3") (pinfunction "D1_3") (pintype "passive"))
      (node (ref "Q5") (pin "4") (pinfunction "D1_4") (pintype "passive"))
      (node (ref "Q5") (pin "9") (pinfunction "D1_9") (pintype "passive"))
      (node (ref "Q6") (pin "2") (pinfunction "D1_2") (pintype "passive"))
      (node (ref "Q6") (pin "3") (pinfunction "D1_3") (pintype "passive"))
      (node (ref "Q6") (pin "4") (pinfunction "D1_4") (pintype "passive"))
      (node (ref "Q6") (pin "9") (pinfunction "D1_9") (pintype "passive"))
      (node (ref "Q7") (pin "2") (pinfunction "D1_2") (pintype "passive"))
      (node (ref "Q7") (pin "3") (pinfunction "D1_3") (pintype "passive"))
      (node (ref "Q7") (pin "4") (pinfunction "D1_4") (pintype "passive"))
      (node (ref "Q7") (pin "9") (pinfunction "D1_9") (pintype "passive"))
      (node (ref "Q8") (pin "2") (pinfunction "D1_2") (pintype "passive"))
      (node (ref "Q8") (pin "3") (pinfunction "D1_3") (pintype "passive"))
      (node (ref "Q8") (pin "4") (pinfunction "D1_4") (pintype "passive"))
      (node (ref "Q8") (pin "9") (pinfunction "D1_9") (pintype "passive"))
      (node (ref "Q9") (pin "2") (pinfunction "D1_2") (pintype "passive"))
      (node (ref "Q9") (pin "3") (pinfunction "D1_3") (pintype "passive"))
      (node (ref "Q9") (pin "4") (pinfunction "D1_4") (pintype "passive"))
      (node (ref "Q9") (pin "9") (pinfunction "D1_9") (pintype "passive"))
    )
    (net (code "133") (name "unconnected-(U2-P0.5-Pad17)") (class "Default")
      (node (ref "U2") (pin "17") (pinfunction "P0.5_17") (pintype "passive+no_connect"))
    )
    (net (code "134") (name "unconnected-(U2-P0.6-Pad16)") (class "Default")
      (node (ref "U2") (pin "16") (pinfunction "P0.6_16") (pintype "passive+no_connect"))
    )
    (net (code "135") (name "unconnected-(U2-P0.7-Pad15)") (class "Default")
      (node (ref "U2") (pin "15") (pinfunction "P0.7_15") (pintype "passive+no_connect"))
    )
    (net (code "136") (name "unconnected-(U2-P1.6-Pad7)") (class "Default")
      (node (ref "U2") (pin "7") (pinfunction "P1.6_7") (pintype "passive+no_connect"))
    )
    (net (code "137") (name "unconnected-(U3-P0.5-Pad17)") (class "Default")
      (node (ref "U3") (pin "17") (pinfunction "P0.5_17") (pintype "passive+no_connect"))
    )
    (net (code "138") (name "unconnected-(U3-P0.6-Pad16)") (class "Default")
      (node (ref "U3") (pin "16") (pinfunction "P0.6_16") (pintype "passive+no_connect"))
    )
    (net (code "139") (name "unconnected-(U3-P0.7-Pad15)") (class "Default")
      (node (ref "U3") (pin "15") (pinfunction "P0.7_15") (pintype "passive+no_connect"))
    )
    (net (code "140") (name "unconnected-(U3-P1.6-Pad7)") (class "Default")
      (node (ref "U3") (pin "7") (pinfunction "P1.6_7") (pintype "passive+no_connect"))
    )
    (net (code "141") (name "unconnected-(U4-P0.5-Pad17)") (class "Default")
      (node (ref "U4") (pin "17") (pinfunction "P0.5_17") (pintype "passive+no_connect"))
    )
    (net (code "142") (name "unconnected-(U4-P0.6-Pad16)") (class "Default")
      (node (ref "U4") (pin "16") (pinfunction "P0.6_16") (pintype "passive+no_connect"))
    )
    (net (code "143") (name "unconnected-(U4-P0.7-Pad15)") (class "Default")
      (node (ref "U4") (pin "15") (pinfunction "P0.7_15") (pintype "passive+no_connect"))
    )
    (net (code "144") (name "unconnected-(U4-P1.6-Pad7)") (class "Default")
      (node (ref "U4") (pin "7") (pinfunction "P1.6_7") (pintype "passive+no_connect"))
    )
    (net (code "145") (name "unconnected-(U5-P0.5-Pad17)") (class "Default")
      (node (ref "U5") (pin "17") (pinfunction "P0.5_17") (pintype "passive+no_connect"))
    )
    (net (code "146") (name "unconnected-(U5-P0.6-Pad16)") (class "Default")
      (node (ref "U5") (pin "16") (pinfunction "P0.6_16") (pintype "passive+no_connect"))
    )
    (net (code "147") (name "unconnected-(U5-P0.7-Pad15)") (class "Default")
      (node (ref "U5") (pin "15") (pinfunction "P0.7_15") (pintype "passive+no_connect"))
    )
    (net (code "148") (name "unconnected-(U5-P1.6-Pad7)") (class "Default")
      (node (ref "U5") (pin "7") (pinfunction "P1.6_7") (pintype "passive+no_connect"))
    )
    (net (code "149") (name "unconnected-(U6-NC-Pad5)") (class "Default")
      (node (ref "U6") (pin "5") (pinfunction "NC_5") (pintype "passive+no_connect"))
    )
    (net (code "150") (name "unconnected-(U6-NC-Pad7)") (class "Default")
      (node (ref "U6") (pin "7") (pinfunction "NC_7") (pintype "passive+no_connect"))
    )
    (net (code "151") (name "unconnected-(U6-NC-Pad8)") (class "Default")
      (node (ref "U6") (pin "8") (pinfunction "NC_8") (pintype "passive+no_connect"))
    )
    (net (code "152") (name "unconnected-(U6-NC-Pad21)") (class "Default")
      (node (ref "U6") (pin "21") (pinfunction "NC_21") (pintype "passive+no_connect"))
    )
    (net (code "153") (name "unconnected-(U7-NC-Pad5)") (class "Default")
      (node (ref "U7") (pin "5") (pinfunction "NC_5") (pintype "passive+no_connect"))
    )
    (net (code "154") (name "unconnected-(U7-NC-Pad7)") (class "Default")
      (node (ref "U7") (pin "7") (pinfunction "NC_7") (pintype "passive+no_connect"))
    )
    (net (code "155") (name "unconnected-(U7-NC-Pad8)") (class "Default")
      (node (ref "U7") (pin "8") (pinfunction "NC_8") (pintype "passive+no_connect"))
    )
    (net (code "156") (name "unconnected-(U7-NC-Pad21)") (class "Default")
      (node (ref "U7") (pin "21") (pinfunction "NC_21") (pintype "passive+no_connect"))
    )
    (net (code "157") (name "unconnected-(U8-NC-Pad5)") (class "Default")
      (node (ref "U8") (pin "5") (pinfunction "NC_5") (pintype "passive+no_connect"))
    )
    (net (code "158") (name "unconnected-(U8-NC-Pad7)") (class "Default")
      (node (ref "U8") (pin "7") (pinfunction "NC_7") (pintype "passive+no_connect"))
    )
    (net (code "159") (name "unconnected-(U8-NC-Pad8)") (class "Default")
      (node (ref "U8") (pin "8") (pinfunction "NC_8") (pintype "passive+no_connect"))
    )
    (net (code "160") (name "unconnected-(U8-NC-Pad21)") (class "Default")
      (node (ref "U8") (pin "21") (pinfunction "NC_21") (pintype "passive+no_connect"))
    )
    (net (code "161") (name "unconnected-(U9-NC-Pad5)") (class "Default")
      (node (ref "U9") (pin "5") (pinfunction "NC_5") (pintype "passive+no_connect"))
    )
    (net (code "162") (name "unconnected-(U9-NC-Pad7)") (class "Default")
      (node (ref "U9") (pin "7") (pinfunction "NC_7") (pintype "passive+no_connect"))
    )
    (net (code "163") (name "unconnected-(U9-NC-Pad8)") (class "Default")
      (node (ref "U9") (pin "8") (pinfunction "NC_8") (pintype "passive+no_connect"))
    )
    (net (code "164") (name "unconnected-(U9-NC-Pad21)") (class "Default")
      (node (ref "U9") (pin "21") (pinfunction "NC_21") (pintype "passive+no_connect"))
    )
  )
)
